# DVT-Discrete-1.net
KiCad netlist of a schematic drawn in Altium Designer
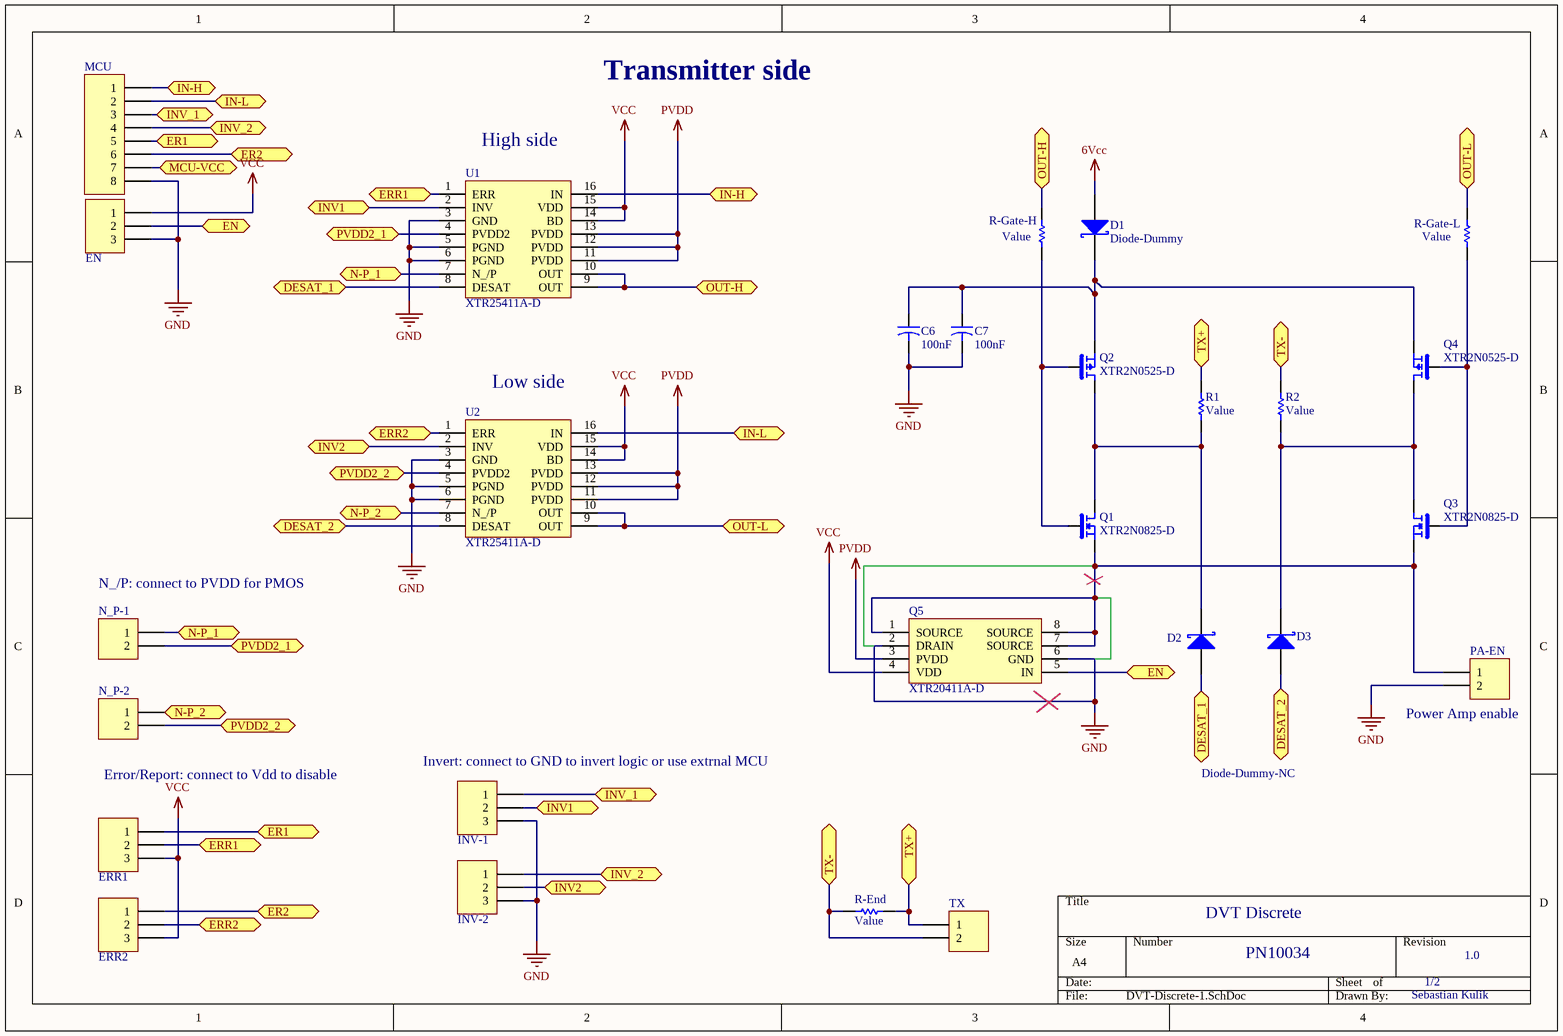
[diagram p0: DVT-Discrete-1.SchDoc]

(export (version "E")
  (design (tool "Eeschema 10.0.6"))
  (components
    (comp (ref "C6")
      (value "100nF")
      (footprint "Dummy-10mm")
      (description "Capacitor-Dummy-THT")
      (fields (field (name "MANUFACTURER") "AVX") (field (name "PUBLISHER") "Sebastian Kulik"))
      (libsource (lib "Capacitors") (part "Capacitor-Dummy-THT"))
    )
    (comp (ref "C7")
      (value "100nF")
      (footprint "Dummy-10mm")
      (description "Capacitor-Dummy-THT")
      (fields (field (name "MANUFACTURER") "AVX") (field (name "PUBLISHER") "Sebastian Kulik"))
      (libsource (lib "Capacitors") (part "Capacitor-Dummy-THT"))
    )
    (comp (ref "D1")
      (value "Diode-Dummy")
      (footprint "DO-15-Dummy")
      (fields (field (name "MANUFACTURER") "COMCHIP TECHNOLOGY") (field (name "PUBLISHER") "Sebastian Kulik"))
      (libsource (lib "Discrete") (part "Diode-Dummy"))
    )
    (comp (ref "D2")
      (value "Diode-Dummy-NC")
      (footprint "DO-15-Dummy")
      (description "Diode-Dummy")
      (fields (field (name "MANUFACTURER") "COMCHIP TECHNOLOGY") (field (name "PUBLISHER") "Sebastian Kulik"))
      (libsource (lib "Discrete") (part "Diode-Dummy"))
    )
    (comp (ref "D3")
      (value "Diode-Dummy")
      (footprint "DO-15-Dummy")
      (fields (field (name "MANUFACTURER") "COMCHIP TECHNOLOGY") (field (name "PUBLISHER") "Sebastian Kulik"))
      (libsource (lib "Discrete") (part "Diode-Dummy"))
    )
    (comp (ref "EN")
      (value "Plug_3_90_2.54")
      (footprint "HDR1X3")
      (description "Plug,-3-Pin")
      (fields (field (name "MANUFACTURER") "WE") (field (name "PUBLISHER") "Sebastian Kulik"))
      (libsource (lib "Connectors") (part "Plug_3_90_2.54"))
    )
    (comp (ref "ERR1")
      (value "Plug_3_90_2.54")
      (footprint "HDR1X3")
      (description "Plug,-3-Pin")
      (fields (field (name "MANUFACTURER") "WE") (field (name "PUBLISHER") "Sebastian Kulik"))
      (libsource (lib "Connectors") (part "Plug_3_90_2.54"))
    )
    (comp (ref "ERR2")
      (value "Plug_3_90_2.54")
      (footprint "HDR1X3")
      (description "Plug,-3-Pin")
      (fields (field (name "MANUFACTURER") "WE") (field (name "PUBLISHER") "Sebastian Kulik"))
      (libsource (lib "Connectors") (part "Plug_3_90_2.54"))
    )
    (comp (ref "INV-1")
      (value "Plug_3_90_2.54")
      (footprint "HDR1X3")
      (description "Plug,-3-Pin")
      (fields (field (name "MANUFACTURER") "WE") (field (name "PUBLISHER") "Sebastian Kulik"))
      (libsource (lib "Connectors") (part "Plug_3_90_2.54"))
    )
    (comp (ref "INV-2")
      (value "Plug_3_90_2.54")
      (footprint "HDR1X3")
      (description "Plug,-3-Pin")
      (fields (field (name "MANUFACTURER") "WE") (field (name "PUBLISHER") "Sebastian Kulik"))
      (libsource (lib "Connectors") (part "Plug_3_90_2.54"))
    )
    (comp (ref "MCU")
      (value "Plug_08_2.54")
      (footprint "HDR1X8_2.54")
      (description "Plug, 08-Pin")
      (fields (field (name "MANUFACTURER") "WE") (field (name "PUBLISHER") "Sebastian Kulik"))
      (libsource (lib "Connectors") (part "Plug_08_2.54"))
    )
    (comp (ref "N_P-1")
      (value "Plug_2_90_2.54")
      (footprint "HDR1X2")
      (description "Plug, 2-Pin")
      (fields (field (name "MANUFACTURER") "WE") (field (name "PUBLISHER") "Sebastian Kulik"))
      (libsource (lib "Connectors") (part "Plug_2_90_2.54"))
    )
    (comp (ref "N_P-2")
      (value "Plug_2_90_2.54")
      (footprint "HDR1X2")
      (description "Plug, 2-Pin")
      (fields (field (name "MANUFACTURER") "WE") (field (name "PUBLISHER") "Sebastian Kulik"))
      (libsource (lib "Connectors") (part "Plug_2_90_2.54"))
    )
    (comp (ref "PA-EN")
      (value "Plug_2_90_2.54")
      (footprint "HDR1X2")
      (description "Plug, 2-Pin")
      (fields (field (name "MANUFACTURER") "WE") (field (name "PUBLISHER") "Sebastian Kulik"))
      (libsource (lib "") (part "Plug_2_90_2.54_1"))
    )
    (comp (ref "Q1")
      (value "XTR2N0825-D")
      (footprint "DIP-8-Ceramic-HT")
      (description "N-FET, 80V@ 4A")
      (fields (field (name "MANUFACTURER") "TI") (field (name "PUBLISHER") "Sebastian Kulik"))
      (libsource (lib "Discrete") (part "XTR2N0825-D"))
    )
    (comp (ref "Q2")
      (value "XTR2N0525-D")
      (footprint "DIP-8-Ceramic-HT")
      (description "P-FET, 50V@ 4A")
      (fields (field (name "MANUFACTURER") "TI") (field (name "PUBLISHER") "Sebastian Kulik"))
      (libsource (lib "Discrete") (part "XTR2N0525-D"))
    )
    (comp (ref "Q3")
      (value "XTR2N0825-D")
      (footprint "DIP-8-Ceramic-HT")
      (description "N-FET, 80V@ 4A")
      (fields (field (name "MANUFACTURER") "TI") (field (name "PUBLISHER") "Sebastian Kulik"))
      (libsource (lib "Discrete") (part "XTR2N0825-D"))
    )
    (comp (ref "Q4")
      (value "XTR2N0525-D")
      (footprint "DIP-8-Ceramic-HT")
      (description "P-FET, 50V@ 4A")
      (fields (field (name "MANUFACTURER") "TI") (field (name "PUBLISHER") "Sebastian Kulik"))
      (libsource (lib "Discrete") (part "XTR2N0525-D"))
    )
    (comp (ref "Q5")
      (value "XTR20411A-D")
      (footprint "DIP-8-Ceramic-HT")
      (description "Gate driver")
      (fields (field (name "MANUFACTURER") "X-Rel") (field (name "PUBLISHER") "Sebastian Kulik"))
      (libsource (lib "ICs") (part "XTR20411A-D"))
    )
    (comp (ref "R-End")
      (value "Value")
      (footprint "Dummy-10mm")
      (description "Resistor-Dummy-THT")
      (fields (field (name "PUBLISHER") "Sebastian Kulik"))
      (libsource (lib "Resistors") (part "Resistor-Dummy-THT"))
    )
    (comp (ref "R-Gate-H")
      (value "Value")
      (footprint "Dummy-10mm")
      (description "Resistor-Dummy-THT")
      (fields (field (name "PUBLISHER") "Sebastian Kulik"))
      (libsource (lib "Resistors") (part "Resistor-Dummy-THT"))
    )
    (comp (ref "R-Gate-L")
      (value "Value")
      (footprint "Dummy-10mm")
      (description "Resistor-Dummy-THT")
      (fields (field (name "PUBLISHER") "Sebastian Kulik"))
      (libsource (lib "Resistors") (part "Resistor-Dummy-THT"))
    )
    (comp (ref "R1")
      (value "Value")
      (footprint "Dummy-15mm")
      (description "Resistor-Dummy-THT")
      (fields (field (name "PUBLISHER") "Sebastian Kulik"))
      (libsource (lib "Resistors") (part "Resistor-Dummy-THT"))
    )
    (comp (ref "R2")
      (value "Value")
      (footprint "Dummy-15mm")
      (description "Resistor-Dummy-THT")
      (fields (field (name "PUBLISHER") "Sebastian Kulik"))
      (libsource (lib "Resistors") (part "Resistor-Dummy-THT"))
    )
    (comp (ref "TX")
      (value "PHOENIX_1715721")
      (footprint "Phoenix-2-5_08")
      (description "Phoenix, 2 pol, 5.08mm, 22A, 715721")
      (fields (field (name "MANUFACTURER") "Phoenix") (field (name "PUBLISHER") "Sebastian Kulik"))
      (libsource (lib "Connectors") (part "2Pol_1715721"))
    )
    (comp (ref "U1")
      (value "XTR25411A-D")
      (footprint "DIP-16-Ceramic-HT")
      (description "Gate driver")
      (fields (field (name "MANUFACTURER") "X-Rel") (field (name "PUBLISHER") "Sebastian Kulik"))
      (libsource (lib "ICs") (part "XTR25411A-D"))
    )
    (comp (ref "U2")
      (value "XTR25411A-D")
      (footprint "DIP-16-Ceramic-HT")
      (description "Gate driver")
      (fields (field (name "MANUFACTURER") "X-Rel") (field (name "PUBLISHER") "Sebastian Kulik"))
      (libsource (lib "ICs") (part "XTR25411A-D"))
    )
  )
  (nets
    (net (code "1") (name "/DESAT_1") (class "Default")
      (node (ref "D2") (pin "2") (pinfunction "A_2") (pintype "passive"))
      (node (ref "U1") (pin "8") (pinfunction "DESAT_8") (pintype "passive"))
    )
    (net (code "2") (name "/DESAT_2") (class "Default")
      (node (ref "D3") (pin "2") (pinfunction "A_2") (pintype "passive"))
      (node (ref "U2") (pin "8") (pinfunction "DESAT_8") (pintype "passive"))
    )
    (net (code "3") (name "/EN") (class "Default")
      (node (ref "EN") (pin "2") (pinfunction "2_2") (pintype "passive"))
      (node (ref "Q5") (pin "5") (pinfunction "IN_5") (pintype "passive"))
    )
    (net (code "4") (name "/ER1") (class "Default")
      (node (ref "ERR1") (pin "1") (pinfunction "1_1") (pintype "passive"))
      (node (ref "MCU") (pin "5") (pinfunction "5_5") (pintype "passive"))
    )
    (net (code "5") (name "/ER2") (class "Default")
      (node (ref "ERR2") (pin "1") (pinfunction "1_1") (pintype "passive"))
      (node (ref "MCU") (pin "6") (pinfunction "6_6") (pintype "passive"))
    )
    (net (code "6") (name "/ERR1") (class "Default")
      (node (ref "ERR1") (pin "2") (pinfunction "2_2") (pintype "passive"))
      (node (ref "U1") (pin "1") (pinfunction "ERR_1") (pintype "passive"))
    )
    (net (code "7") (name "/ERR2") (class "Default")
      (node (ref "ERR2") (pin "2") (pinfunction "2_2") (pintype "passive"))
      (node (ref "U2") (pin "1") (pinfunction "ERR_1") (pintype "passive"))
    )
    (net (code "8") (name "/IN-H") (class "Default")
      (node (ref "MCU") (pin "1") (pinfunction "1_1") (pintype "passive"))
      (node (ref "U1") (pin "16") (pinfunction "IN_16") (pintype "passive"))
    )
    (net (code "9") (name "/IN-L") (class "Default")
      (node (ref "MCU") (pin "2") (pinfunction "2_2") (pintype "passive"))
      (node (ref "U2") (pin "16") (pinfunction "IN_16") (pintype "passive"))
    )
    (net (code "10") (name "/INV1") (class "Default")
      (node (ref "INV-1") (pin "2") (pinfunction "2_2") (pintype "passive"))
      (node (ref "U1") (pin "2") (pinfunction "INV_2") (pintype "passive"))
    )
    (net (code "11") (name "/INV2") (class "Default")
      (node (ref "INV-2") (pin "2") (pinfunction "2_2") (pintype "passive"))
      (node (ref "U2") (pin "2") (pinfunction "INV_2") (pintype "passive"))
    )
    (net (code "12") (name "/INV_1") (class "Default")
      (node (ref "INV-1") (pin "1") (pinfunction "1_1") (pintype "passive"))
      (node (ref "MCU") (pin "3") (pinfunction "3_3") (pintype "passive"))
    )
    (net (code "13") (name "/INV_2") (class "Default")
      (node (ref "INV-2") (pin "1") (pinfunction "1_1") (pintype "passive"))
      (node (ref "MCU") (pin "4") (pinfunction "4_4") (pintype "passive"))
    )
    (net (code "14") (name "/MCU-VCC") (class "Default")
      (node (ref "MCU") (pin "7") (pinfunction "7_7") (pintype "passive"))
    )
    (net (code "15") (name "/N-P_1") (class "Default")
      (node (ref "N_P-1") (pin "1") (pinfunction "1_1") (pintype "passive"))
      (node (ref "U1") (pin "7") (pinfunction "N_/P_7") (pintype "passive"))
    )
    (net (code "16") (name "/N-P_2") (class "Default")
      (node (ref "N_P-2") (pin "1") (pinfunction "1_1") (pintype "passive"))
      (node (ref "U2") (pin "7") (pinfunction "N_/P_7") (pintype "passive"))
    )
    (net (code "17") (name "/OUT-H") (class "Default")
      (node (ref "R-Gate-H") (pin "2") (pinfunction "2_2") (pintype "passive"))
      (node (ref "U1") (pin "10") (pinfunction "OUT_10") (pintype "passive"))
      (node (ref "U1") (pin "9") (pinfunction "OUT_9") (pintype "passive"))
    )
    (net (code "18") (name "/OUT-L") (class "Default")
      (node (ref "R-Gate-L") (pin "2") (pinfunction "2_2") (pintype "passive"))
      (node (ref "U2") (pin "10") (pinfunction "OUT_10") (pintype "passive"))
      (node (ref "U2") (pin "9") (pinfunction "OUT_9") (pintype "passive"))
    )
    (net (code "19") (name "/PVDD2_1") (class "Default")
      (node (ref "N_P-1") (pin "2") (pinfunction "2_2") (pintype "passive"))
      (node (ref "U1") (pin "4") (pinfunction "PVDD2_4") (pintype "passive"))
    )
    (net (code "20") (name "/PVDD2_2") (class "Default")
      (node (ref "N_P-2") (pin "2") (pinfunction "2_2") (pintype "passive"))
      (node (ref "U2") (pin "4") (pinfunction "PVDD2_4") (pintype "passive"))
    )
    (net (code "21") (name "/TX+") (class "Default")
      (node (ref "R-End") (pin "2") (pinfunction "2_2") (pintype "passive"))
      (node (ref "R1") (pin "2") (pinfunction "2_2") (pintype "passive"))
      (node (ref "TX") (pin "1") (pinfunction "1_1") (pintype "passive"))
    )
    (net (code "22") (name "/TX-") (class "Default")
      (node (ref "R-End") (pin "1") (pinfunction "1_1") (pintype "passive"))
      (node (ref "R2") (pin "2") (pinfunction "2_2") (pintype "passive"))
      (node (ref "TX") (pin "2") (pinfunction "2_2") (pintype "passive"))
    )
    (net (code "23") (name "6Vcc") (class "Default")
      (node (ref "D1") (pin "2") (pinfunction "A_2") (pintype "passive"))
    )
    (net (code "24") (name "GND") (class "Default")
      (node (ref "C6") (pin "2") (pinfunction "2_2") (pintype "passive"))
      (node (ref "C7") (pin "2") (pinfunction "2_2") (pintype "passive"))
      (node (ref "EN") (pin "3") (pinfunction "3_3") (pintype "passive"))
      (node (ref "INV-1") (pin "3") (pinfunction "3_3") (pintype "passive"))
      (node (ref "INV-2") (pin "3") (pinfunction "3_3") (pintype "passive"))
      (node (ref "MCU") (pin "8") (pinfunction "8_8") (pintype "passive"))
      (node (ref "PA-EN") (pin "2") (pinfunction "2_2") (pintype "passive"))
      (node (ref "Q5") (pin "2") (pinfunction "DRAIN_2") (pintype "passive"))
      (node (ref "Q5") (pin "6") (pinfunction "GND_6") (pintype "passive"))
      (node (ref "U1") (pin "3") (pinfunction "GND_3") (pintype "passive"))
      (node (ref "U1") (pin "5") (pinfunction "PGND_5") (pintype "passive"))
      (node (ref "U1") (pin "6") (pinfunction "PGND_6") (pintype "passive"))
      (node (ref "U2") (pin "3") (pinfunction "GND_3") (pintype "passive"))
      (node (ref "U2") (pin "5") (pinfunction "PGND_5") (pintype "passive"))
      (node (ref "U2") (pin "6") (pinfunction "PGND_6") (pintype "passive"))
    )
    (net (code "25") (name "Net-(D1-K)") (class "Default")
      (node (ref "C6") (pin "1") (pinfunction "1_1") (pintype "passive"))
      (node (ref "C7") (pin "1") (pinfunction "1_1") (pintype "passive"))
      (node (ref "D1") (pin "1") (pinfunction "K_1") (pintype "passive"))
      (node (ref "Q2") (pin "1") (pinfunction "Source_1") (pintype "passive"))
      (node (ref "Q4") (pin "1") (pinfunction "Source_1") (pintype "passive"))
    )
    (net (code "26") (name "Net-(D2-K)") (class "Default")
      (node (ref "D2") (pin "1") (pinfunction "K_1") (pintype "passive"))
      (node (ref "Q1") (pin "5") (pinfunction "Drain_5") (pintype "passive"))
      (node (ref "Q2") (pin "5") (pinfunction "Drain_5") (pintype "passive"))
      (node (ref "R1") (pin "1") (pinfunction "1_1") (pintype "passive"))
    )
    (net (code "27") (name "Net-(D3-K)") (class "Default")
      (node (ref "D3") (pin "1") (pinfunction "K_1") (pintype "passive"))
      (node (ref "Q3") (pin "5") (pinfunction "Drain_5") (pintype "passive"))
      (node (ref "Q4") (pin "5") (pinfunction "Drain_5") (pintype "passive"))
      (node (ref "R2") (pin "1") (pinfunction "1_1") (pintype "passive"))
    )
    (net (code "28") (name "Net-(Q1-Gate)") (class "Default")
      (node (ref "Q1") (pin "4") (pinfunction "Gate_4") (pintype "passive"))
      (node (ref "Q2") (pin "4") (pinfunction "Gate_4") (pintype "passive"))
      (node (ref "R-Gate-H") (pin "1") (pinfunction "1_1") (pintype "passive"))
    )
    (net (code "29") (name "Net-(Q1-Source)") (class "Default")
      (node (ref "PA-EN") (pin "1") (pinfunction "1_1") (pintype "passive"))
      (node (ref "Q1") (pin "1") (pinfunction "Source_1") (pintype "passive"))
      (node (ref "Q3") (pin "1") (pinfunction "Source_1") (pintype "passive"))
      (node (ref "Q5") (pin "1") (pinfunction "SOURCE_1") (pintype "passive"))
      (node (ref "Q5") (pin "7") (pinfunction "SOURCE_7") (pintype "passive"))
      (node (ref "Q5") (pin "8") (pinfunction "SOURCE_8") (pintype "passive"))
    )
    (net (code "30") (name "Net-(Q3-Gate)") (class "Default")
      (node (ref "Q3") (pin "4") (pinfunction "Gate_4") (pintype "passive"))
      (node (ref "Q4") (pin "4") (pinfunction "Gate_4") (pintype "passive"))
      (node (ref "R-Gate-L") (pin "1") (pinfunction "1_1") (pintype "passive"))
    )
    (net (code "31") (name "PVDD") (class "Default")
      (node (ref "Q5") (pin "3") (pinfunction "PVDD_3") (pintype "passive"))
      (node (ref "U1") (pin "11") (pinfunction "PVDD_11") (pintype "passive"))
      (node (ref "U1") (pin "12") (pinfunction "PVDD_12") (pintype "passive"))
      (node (ref "U1") (pin "13") (pinfunction "PVDD_13") (pintype "passive"))
      (node (ref "U2") (pin "11") (pinfunction "PVDD_11") (pintype "passive"))
      (node (ref "U2") (pin "12") (pinfunction "PVDD_12") (pintype "passive"))
      (node (ref "U2") (pin "13") (pinfunction "PVDD_13") (pintype "passive"))
    )
    (net (code "32") (name "VCC") (class "Default")
      (node (ref "EN") (pin "1") (pinfunction "1_1") (pintype "passive"))
      (node (ref "ERR1") (pin "3") (pinfunction "3_3") (pintype "passive"))
      (node (ref "ERR2") (pin "3") (pinfunction "3_3") (pintype "passive"))
      (node (ref "Q5") (pin "4") (pinfunction "VDD_4") (pintype "passive"))
      (node (ref "U1") (pin "14") (pinfunction "BD_14") (pintype "passive"))
      (node (ref "U1") (pin "15") (pinfunction "VDD_15") (pintype "passive"))
      (node (ref "U2") (pin "14") (pinfunction "BD_14") (pintype "passive"))
      (node (ref "U2") (pin "15") (pinfunction "VDD_15") (pintype "passive"))
    )
  )
)
